# Top_Level.net
KiCad netlist of a schematic drawn in Altium Designer
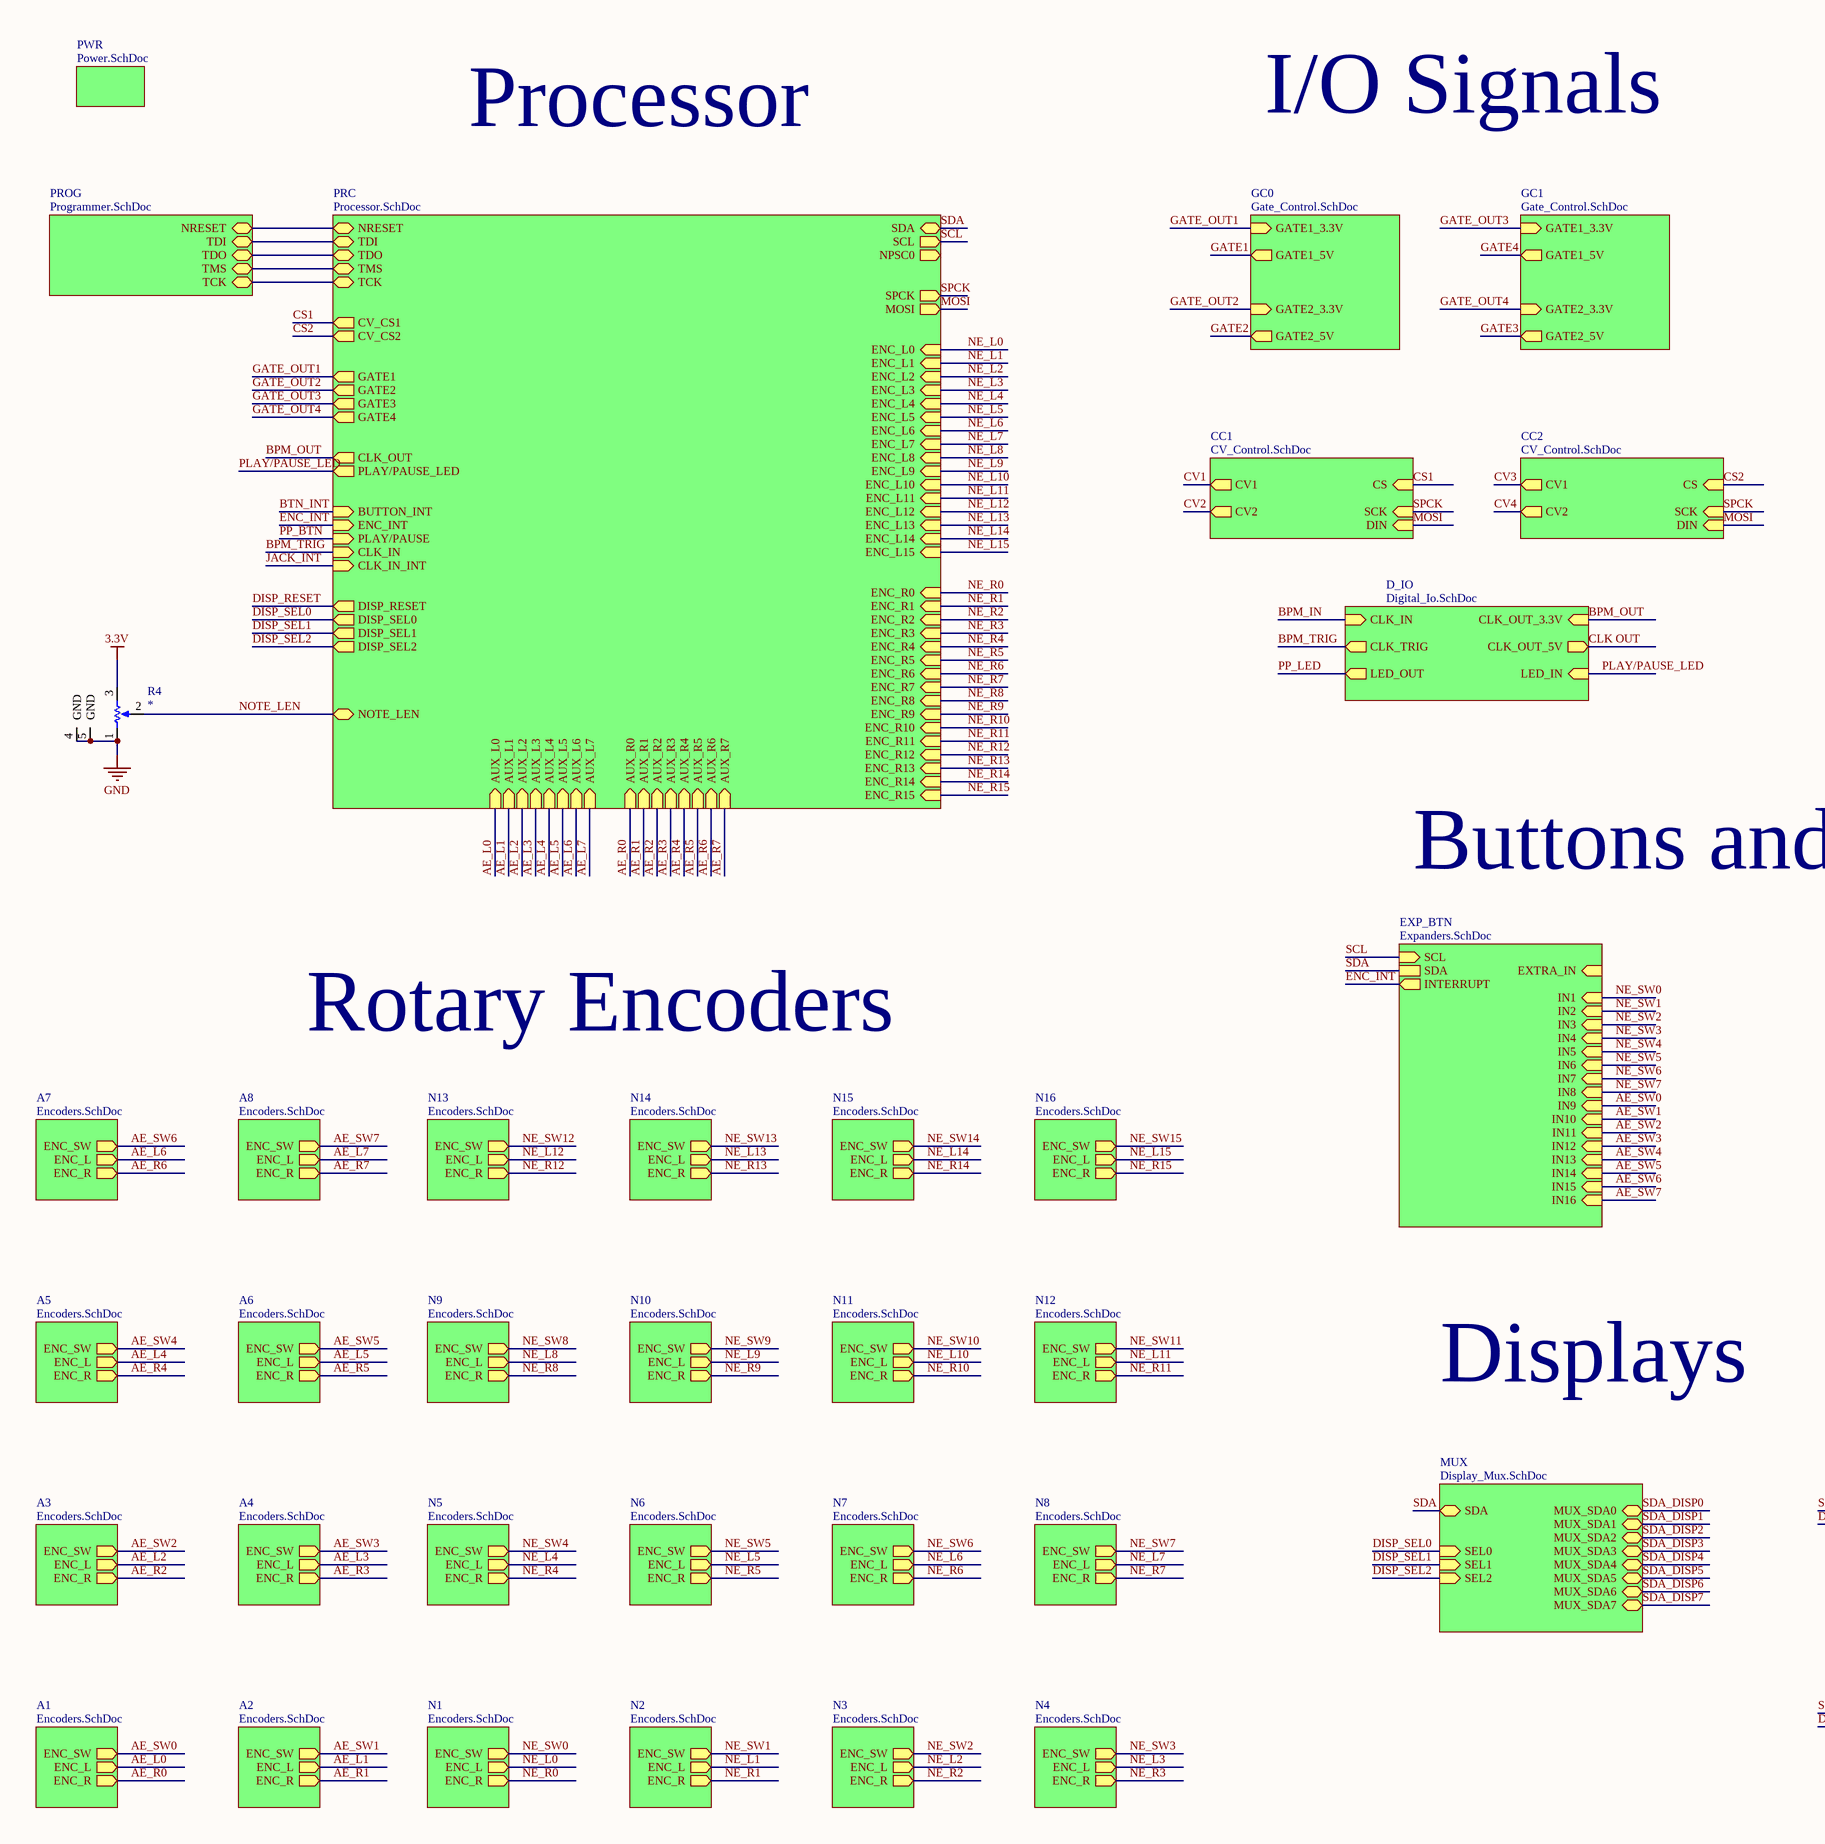
[diagram p0: Top_Level.SchDoc, left]
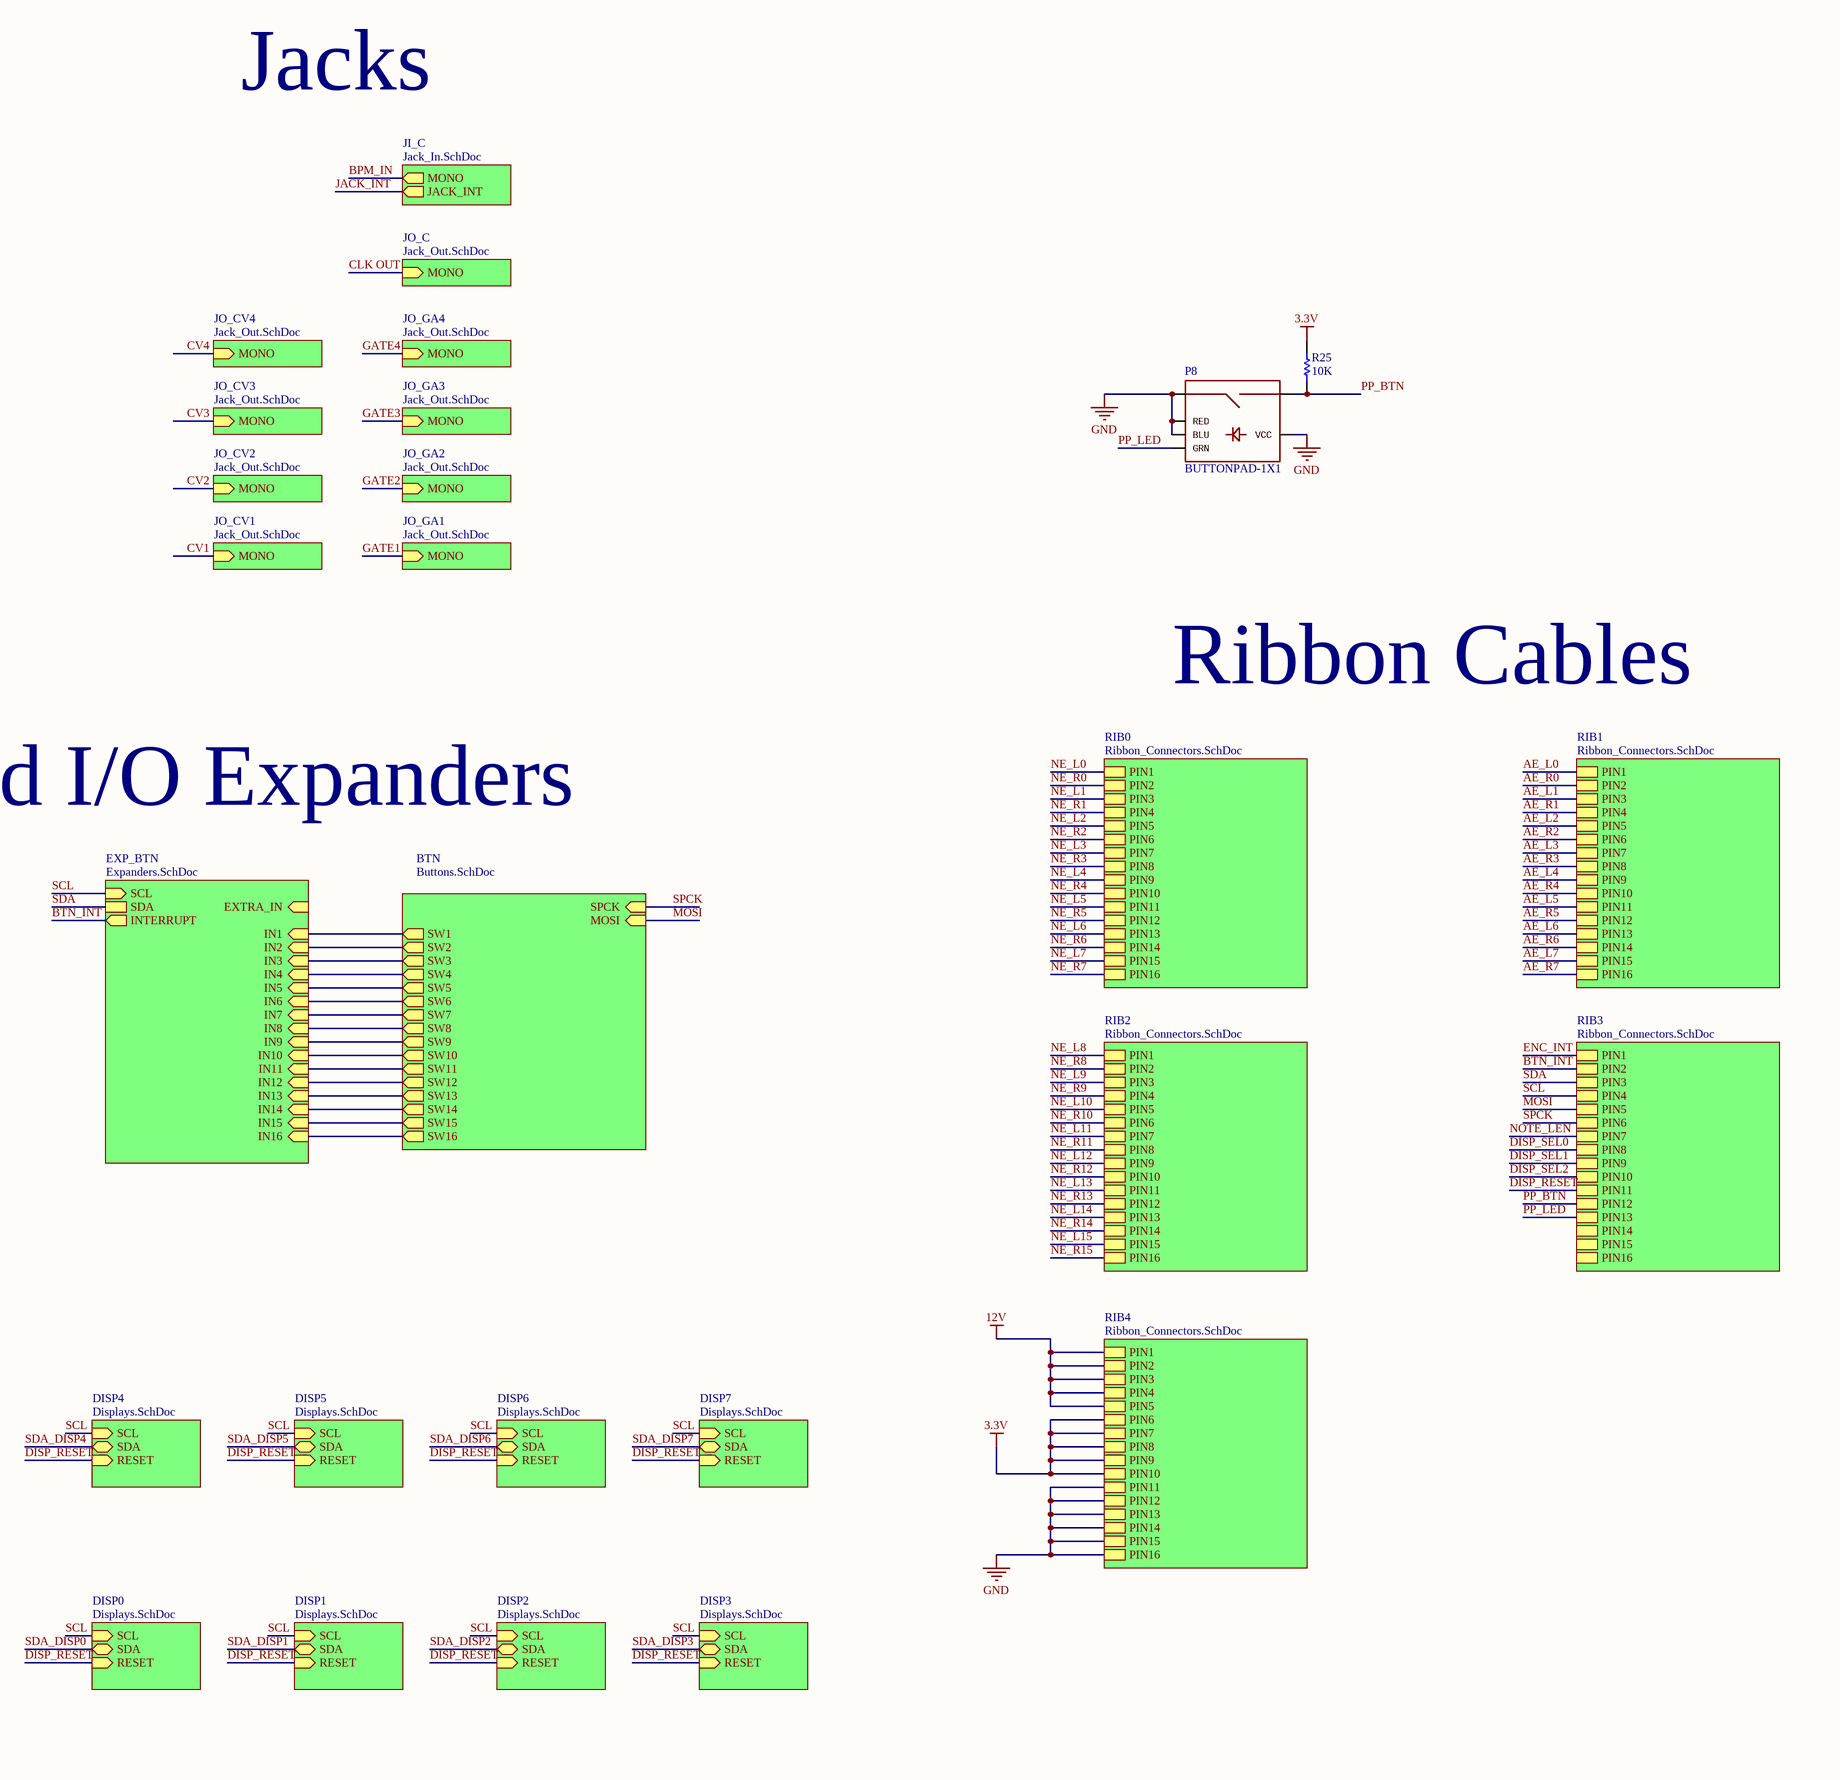
[diagram p1: Top_Level.SchDoc, right]

(export (version "E")
  (design (tool "Eeschema 10.0.6"))
  (components
    (comp (ref "P8")
      (value "BUTTONPAD-1X1")
      (footprint "BUTTONPAD-1X1")
      (libsource (lib "Button_Pad_Breakout-v05") (part "BUTTONPAD-1X1"))
    )
    (comp (ref "R4")
      (value "*")
      (footprint "Potentiometer (NO SLOT)")
      (libsource (lib "FlexControl") (part "Potentiometer (NO_SLOTS)"))
    )
    (comp (ref "R25")
      (value "10K")
      (footprint "AXIAL-0.3")
      (description "Resistor")
      (fields (field (name "Comment") "R3") (field (name "PUBLISHER") "Altium Limited"))
      (libsource (lib "Miscellaneous Devices") (part "Res1"))
    )
  )
  (nets
    (net (code "101") (name "/NOTE_LEN") (class "Default")
      (node (ref "R4") (pin "2") (pinfunction "TAP_2") (pintype "passive"))
    )
    (net (code "108") (name "/PP_BTN") (class "Default")
      (node (ref "P8") (pin "SIG2") (pinfunction "SIG2_SIG2") (pintype "passive"))
      (node (ref "R25") (pin "1") (pinfunction "1_1") (pintype "passive"))
    )
    (net (code "109") (name "/PP_LED") (class "Default")
      (node (ref "P8") (pin "GRN1") (pinfunction "GRN_GRN1") (pintype "passive"))
    )
    (net (code "141") (name "3.3V") (class "Default")
      (node (ref "R25") (pin "2") (pinfunction "2_2") (pintype "passive"))
      (node (ref "R4") (pin "3") (pinfunction "BOT_3") (pintype "passive"))
    )
    (net (code "143") (name "GND") (class "Default")
      (node (ref "P8") (pin "BLU1") (pinfunction "BLU_BLU1") (pintype "passive"))
      (node (ref "P8") (pin "RED1") (pinfunction "RED_RED1") (pintype "passive"))
      (node (ref "P8") (pin "SIG1") (pinfunction "SIG1_SIG1") (pintype "passive"))
      (node (ref "P8") (pin "VCC1") (pinfunction "VCC_VCC1") (pintype "passive"))
      (node (ref "R4") (pin "1") (pinfunction "TOP_1") (pintype "passive"))
      (node (ref "R4") (pin "4") (pinfunction "GND_4") (pintype "passive"))
      (node (ref "R4") (pin "5") (pinfunction "GND_5") (pintype "passive"))
    )
  )
)
